# PassStat.net
KiCad netlist of a schematic drawn in Altium Designer
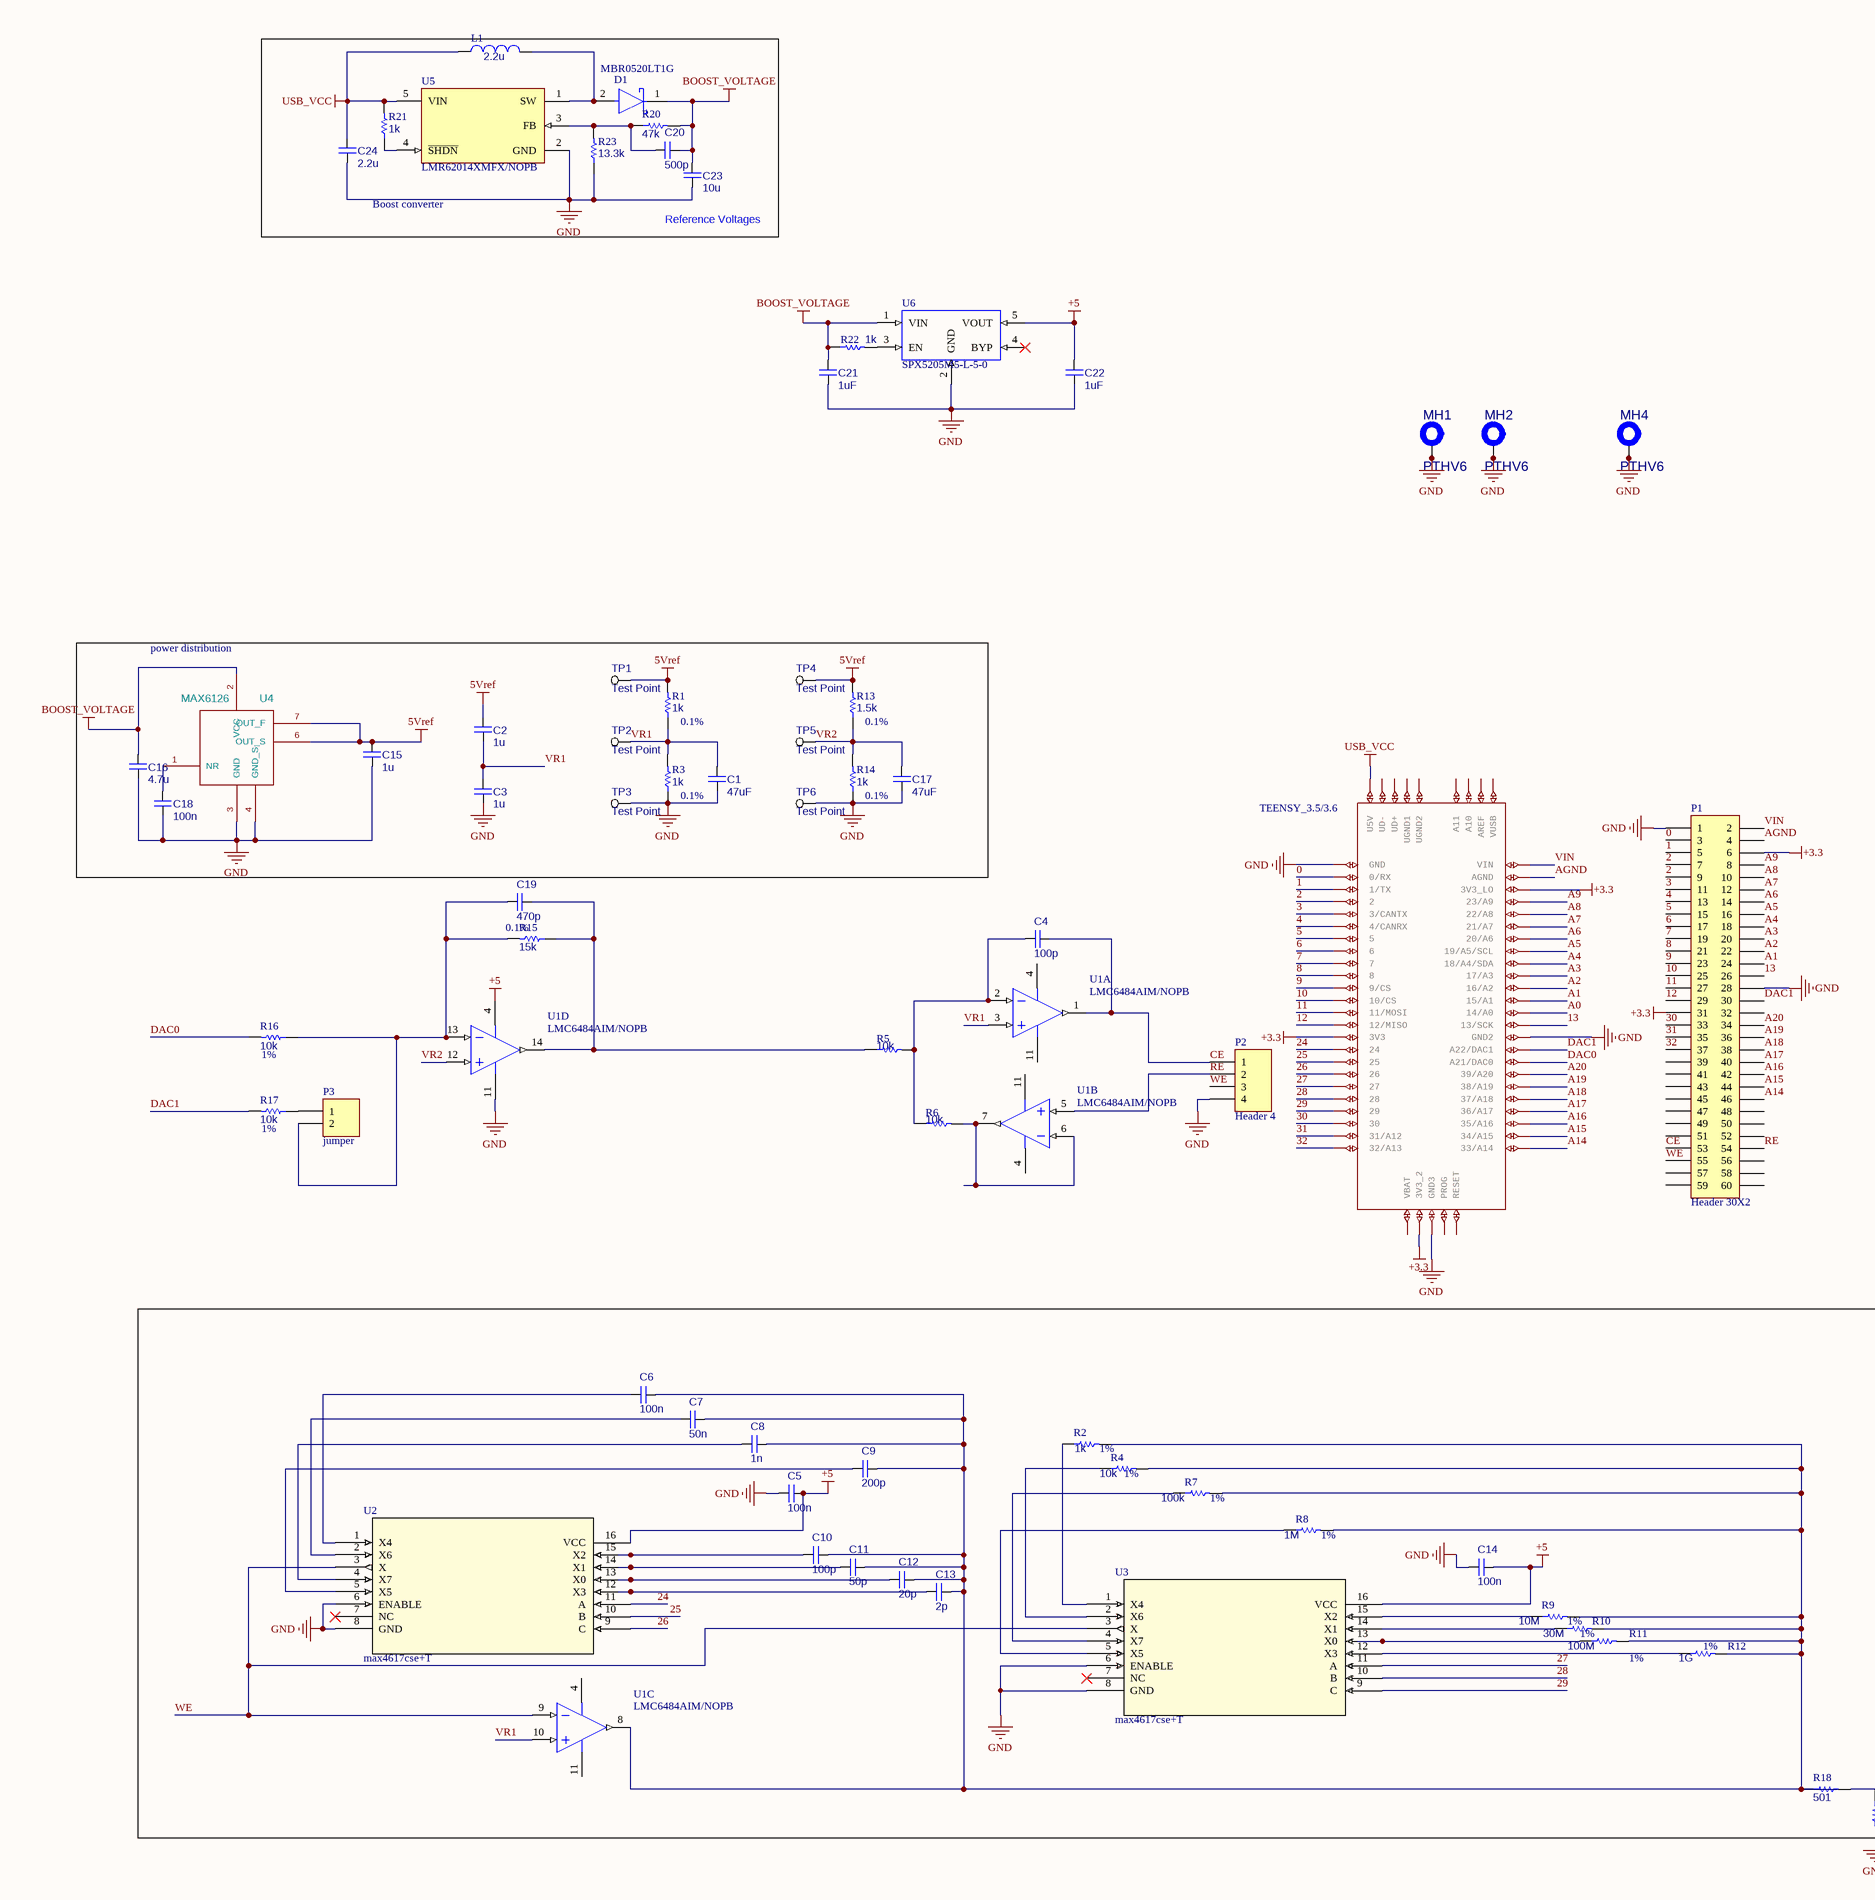
[diagram p0: PassStat.SchDoc, left]
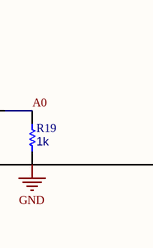
[diagram p1: PassStat.SchDoc, right]

(export (version "E")
  (design (tool "Eeschema 10.0.6"))
  (components
    (comp (ref "C1")
      (value "47uF")
      (footprint "C0805A")
      (description "Non-polarized capacitor")
      (fields (field (name "Comment") "Capacitor"))
      (libsource (lib "Space Concordia") (part "Capacitor"))
    )
    (comp (ref "C2")
      (value "1u")
      (footprint "C0805A")
      (description "Non-polarized capacitor")
      (fields (field (name "Comment") "Capacitor"))
      (libsource (lib "Space Concordia") (part "Capacitor"))
    )
    (comp (ref "C3")
      (value "1u")
      (footprint "C0805A")
      (description "Non-polarized capacitor")
      (fields (field (name "Comment") "Capacitor"))
      (libsource (lib "Space Concordia") (part "Capacitor"))
    )
    (comp (ref "C4")
      (value "100p")
      (footprint "C0805A")
      (description "Non-polarized capacitor")
      (fields (field (name "Comment") "Capacitor"))
      (libsource (lib "Space Concordia") (part "Capacitor"))
    )
    (comp (ref "C5")
      (value "100n")
      (footprint "C0805A")
      (description "Non-polarized capacitor")
      (fields (field (name "Comment") "Capacitor"))
      (libsource (lib "Space Concordia") (part "Capacitor"))
    )
    (comp (ref "C6")
      (value "100n")
      (footprint "C0805A")
      (description "Non-polarized capacitor")
      (fields (field (name "Comment") "Capacitor"))
      (libsource (lib "Space Concordia") (part "Capacitor"))
    )
    (comp (ref "C7")
      (value "50n")
      (footprint "C0805A")
      (description "Non-polarized capacitor")
      (fields (field (name "Comment") "Capacitor"))
      (libsource (lib "Space Concordia") (part "Capacitor"))
    )
    (comp (ref "C8")
      (value "1n")
      (footprint "C0805A")
      (description "Non-polarized capacitor")
      (fields (field (name "Comment") "Capacitor"))
      (libsource (lib "Space Concordia") (part "Capacitor"))
    )
    (comp (ref "C9")
      (value "200p")
      (footprint "C0805A")
      (description "Non-polarized capacitor")
      (fields (field (name "Comment") "Capacitor"))
      (libsource (lib "Space Concordia") (part "Capacitor"))
    )
    (comp (ref "C10")
      (value "100p")
      (footprint "C0805A")
      (description "Non-polarized capacitor")
      (fields (field (name "Comment") "Capacitor"))
      (libsource (lib "Space Concordia") (part "Capacitor"))
    )
    (comp (ref "C11")
      (value "50p")
      (footprint "C0805A")
      (description "Non-polarized capacitor")
      (fields (field (name "Comment") "Capacitor"))
      (libsource (lib "Space Concordia") (part "Capacitor"))
    )
    (comp (ref "C12")
      (value "20p")
      (footprint "C0805A")
      (description "Non-polarized capacitor")
      (fields (field (name "Comment") "Capacitor"))
      (libsource (lib "Space Concordia") (part "Capacitor"))
    )
    (comp (ref "C13")
      (value "2p")
      (footprint "C0805A")
      (description "Non-polarized capacitor")
      (fields (field (name "Comment") "Capacitor"))
      (libsource (lib "Space Concordia") (part "Capacitor"))
    )
    (comp (ref "C14")
      (value "100n")
      (footprint "C0805A")
      (description "Non-polarized capacitor")
      (fields (field (name "Comment") "Capacitor"))
      (libsource (lib "Space Concordia") (part "Capacitor"))
    )
    (comp (ref "C15")
      (value "1u")
      (footprint "C0805A")
      (description "Non-polarized capacitor")
      (fields (field (name "Comment") "Capacitor"))
      (libsource (lib "Space Concordia") (part "Capacitor"))
    )
    (comp (ref "C16")
      (value "4.7u")
      (footprint "C0805A")
      (description "Non-polarized capacitor")
      (fields (field (name "Comment") "Capacitor"))
      (libsource (lib "Space Concordia") (part "Capacitor"))
    )
    (comp (ref "C17")
      (value "47uF")
      (footprint "C0805A")
      (description "Non-polarized capacitor")
      (fields (field (name "Comment") "Capacitor"))
      (libsource (lib "Space Concordia") (part "Capacitor"))
    )
    (comp (ref "C18")
      (value "100n")
      (footprint "C0805A")
      (description "Non-polarized capacitor")
      (fields (field (name "Comment") "Capacitor"))
      (libsource (lib "Space Concordia") (part "Capacitor"))
    )
    (comp (ref "C19")
      (value "470p")
      (footprint "C0805A")
      (description "Non-polarized capacitor")
      (fields (field (name "Comment") "Capacitor"))
      (libsource (lib "Space Concordia") (part "Capacitor"))
    )
    (comp (ref "C20")
      (value "500p")
      (footprint "C0805A")
      (description "Non-polarized capacitor")
      (fields (field (name "Comment") "Capacitor"))
      (libsource (lib "Space Concordia") (part "Capacitor"))
    )
    (comp (ref "C21")
      (value "1uF")
      (footprint "C0603A")
      (description "Non-polarized capacitor")
      (fields (field (name "Comment") "Capacitor"))
      (libsource (lib "Space Concordia") (part "Capacitor"))
    )
    (comp (ref "C22")
      (value "1uF")
      (footprint "C0603A")
      (description "Non-polarized capacitor")
      (fields (field (name "Comment") "Capacitor"))
      (libsource (lib "Space Concordia") (part "Capacitor"))
    )
    (comp (ref "C23")
      (value "10u")
      (footprint "C0805A")
      (description "Non-polarized capacitor")
      (fields (field (name "Comment") "Capacitor"))
      (libsource (lib "Space Concordia") (part "Capacitor"))
    )
    (comp (ref "C24")
      (value "2.2u")
      (footprint "C0805A")
      (description "Non-polarized capacitor")
      (fields (field (name "Comment") "Capacitor"))
      (libsource (lib "Space Concordia") (part "Capacitor"))
    )
    (comp (ref "D1")
      (value "MBR0520LT1G")
      (footprint "FP-425-04-IPC_C")
      (description "DIODE SCHOTTKY 20V 500MA SOD123")
      (libsource (lib "Altium Content Vault") (part "1d6ec82d83fb6aee721767c19dac4b9"))
    )
    (comp (ref "L1")
      (value "2.2u")
      (footprint "L0805A")
      (description "Inductor, air coil")
      (fields (field (name "Comment") "2.2uH"))
      (libsource (lib "Space Concordia") (part "Inductor"))
    )
    (comp (ref "MCU")
      (value "TEENSY_3.5/3.6")
      (footprint "TEENSY_3.5/3.6")
      (libsource (lib "Space Concordia") (part "TEENSY_3.5/3.6"))
    )
    (comp (ref "MH1")
      (value "PTHV6")
      (footprint "PTHV6 4-40 Tight")
      (libsource (lib "Space Concordia") (part "PTHV6"))
    )
    (comp (ref "MH2")
      (value "PTHV6")
      (footprint "PTHV6 4-40 Tight")
      (libsource (lib "Space Concordia") (part "PTHV6"))
    )
    (comp (ref "MH4")
      (value "PTHV6")
      (footprint "PTHV6 4-40 Tight")
      (libsource (lib "Space Concordia") (part "PTHV6"))
    )
    (comp (ref "P1")
      (value "Header 30X2")
      (footprint "HDR2X30")
      (description "Header, 30-Pin, Dual row")
      (fields (field (name "PUBLISHER") "Altium Limited"))
      (libsource (lib "Space Concordia") (part "Header 30X2"))
    )
    (comp (ref "P2")
      (value "Header 4")
      (footprint "HDR1X4")
      (description "Header, 4-Pin")
      (fields (field (name "PUBLISHER") "Altium Limited"))
      (libsource (lib "Space Concordia") (part "Header 4H"))
    )
    (comp (ref "P3")
      (value "jumper")
      (footprint "HDR1X2")
      (description "Header, 2-Pin")
      (fields (field (name "PUBLISHER") "Altium Limited"))
      (libsource (lib "Space Concordia") (part "Header 2H"))
    )
    (comp (ref "R1")
      (value "1k")
      (footprint "R0805A")
      (description "Resistor")
      (fields (field (name "TOLERANCE") "0.1%"))
      (libsource (lib "Space Concordia") (part "Resistor"))
    )
    (comp (ref "R2")
      (value "1k")
      (footprint "R0805A")
      (description "Resistor")
      (fields (field (name "TOLERANCE") "1%"))
      (libsource (lib "Space Concordia") (part "Resistor"))
    )
    (comp (ref "R3")
      (value "1k")
      (footprint "R0805A")
      (description "Resistor")
      (fields (field (name "TOLERANCE") "0.1%"))
      (libsource (lib "Space Concordia") (part "Resistor"))
    )
    (comp (ref "R4")
      (value "10k")
      (footprint "R0805A")
      (description "Resistor")
      (fields (field (name "TOLERANCE") "1%"))
      (libsource (lib "Space Concordia") (part "Resistor"))
    )
    (comp (ref "R5")
      (value "10k")
      (footprint "R0805A")
      (description "Resistor")
      (libsource (lib "Space Concordia") (part "Resistor"))
    )
    (comp (ref "R6")
      (value "10k")
      (footprint "R0805A")
      (description "Resistor")
      (libsource (lib "Space Concordia") (part "Resistor"))
    )
    (comp (ref "R7")
      (value "100k")
      (footprint "R0805A")
      (description "Resistor")
      (fields (field (name "TOLERANCE") "1%"))
      (libsource (lib "Space Concordia") (part "Resistor"))
    )
    (comp (ref "R8")
      (value "1M")
      (footprint "R0805A")
      (description "Resistor")
      (fields (field (name "TOLERANCE") "1%"))
      (libsource (lib "Space Concordia") (part "Resistor"))
    )
    (comp (ref "R9")
      (value "10M")
      (footprint "R0805A")
      (description "Resistor")
      (fields (field (name "TOLERANCE") "1%"))
      (libsource (lib "Space Concordia") (part "Resistor"))
    )
    (comp (ref "R10")
      (value "30M")
      (footprint "R0805A")
      (description "Resistor")
      (fields (field (name "TOLERANCE") "1%"))
      (libsource (lib "Space Concordia") (part "Resistor"))
    )
    (comp (ref "R11")
      (value "100M")
      (footprint "R0805A")
      (description "Resistor")
      (fields (field (name "TOLERANCE") "1%"))
      (libsource (lib "Space Concordia") (part "Resistor"))
    )
    (comp (ref "R12")
      (value "1G")
      (footprint "R1206A")
      (description "Resistor")
      (fields (field (name "TOLERANCE") "1%"))
      (libsource (lib "Space Concordia") (part "Resistor"))
    )
    (comp (ref "R13")
      (value "1.5k")
      (footprint "R0805A")
      (description "Resistor")
      (fields (field (name "TOLERANCE") "0.1%"))
      (libsource (lib "Space Concordia") (part "Resistor"))
    )
    (comp (ref "R14")
      (value "1k")
      (footprint "R0805A")
      (description "Resistor")
      (fields (field (name "TOLERANCE") "0.1%"))
      (libsource (lib "Space Concordia") (part "Resistor"))
    )
    (comp (ref "R15")
      (value "15k")
      (footprint "R0805A")
      (description "Resistor")
      (fields (field (name "TOLERANCE") "0.1%"))
      (libsource (lib "Space Concordia") (part "Resistor"))
    )
    (comp (ref "R16")
      (value "10k")
      (footprint "R0805A")
      (description "Resistor")
      (fields (field (name "TOLERANCE") "1%"))
      (libsource (lib "Space Concordia") (part "Resistor"))
    )
    (comp (ref "R17")
      (value "10k")
      (footprint "R0805A")
      (description "Resistor")
      (fields (field (name "TOLERANCE") "1%"))
      (libsource (lib "Space Concordia") (part "Resistor"))
    )
    (comp (ref "R18")
      (value "501")
      (footprint "R0805A")
      (description "Resistor")
      (libsource (lib "Space Concordia") (part "Resistor"))
    )
    (comp (ref "R19")
      (value "1k")
      (footprint "R0805A")
      (description "Resistor")
      (libsource (lib "Space Concordia") (part "Resistor"))
    )
    (comp (ref "R20")
      (value "47k")
      (footprint "R0603A")
      (description "Resistor")
      (libsource (lib "Space Concordia") (part "Resistor"))
    )
    (comp (ref "R21")
      (value "1k")
      (footprint "R0603A")
      (description "Resistor")
      (libsource (lib "Space Concordia") (part "Resistor"))
    )
    (comp (ref "R22")
      (value "1k")
      (footprint "R0603A")
      (description "Resistor")
      (libsource (lib "Space Concordia") (part "Resistor"))
    )
    (comp (ref "R23")
      (value "13.3k")
      (footprint "R0603A")
      (description "Resistor")
      (libsource (lib "Space Concordia") (part "Resistor"))
    )
    (comp (ref "TP1")
      (value "Test Point")
      (footprint "TP-SMT-1mm")
      (description "In circuit test point for a net")
      (libsource (lib "Space Concordia") (part "Test Point"))
    )
    (comp (ref "TP2")
      (value "Test Point")
      (footprint "TP-SMT-1mm")
      (description "In circuit test point for a net")
      (libsource (lib "Space Concordia") (part "Test Point"))
    )
    (comp (ref "TP3")
      (value "Test Point")
      (footprint "TP-SMT-1mm")
      (description "In circuit test point for a net")
      (libsource (lib "Space Concordia") (part "Test Point"))
    )
    (comp (ref "TP4")
      (value "Test Point")
      (footprint "TP-SMT-1mm")
      (description "In circuit test point for a net")
      (libsource (lib "Space Concordia") (part "Test Point"))
    )
    (comp (ref "TP5")
      (value "Test Point")
      (footprint "TP-SMT-1mm")
      (description "In circuit test point for a net")
      (libsource (lib "Space Concordia") (part "Test Point"))
    )
    (comp (ref "TP6")
      (value "Test Point")
      (footprint "TP-SMT-1mm")
      (description "In circuit test point for a net")
      (libsource (lib "Space Concordia") (part "Test Point"))
    )
    (comp (ref "U1")
      (value "LMC6484AIM/NOPB")
      (footprint "D0014A_L")
      (description "CMOS Quad Rail to Rail Input and Output Operational Amplifier, 14-pin Narrow SOIC, Pb-Free")
      (fields (field (name "MANUFACTURER") "Texas Instruments"))
      (libsource (lib "Altium Content Vault") (part "AMP-OPA-LF147-14"))
    )
    (comp (ref "U2")
      (value "max4617cse+T")
      (footprint "21-0041_S16+1_MXM")
      (description "No Description Available")
      (libsource (lib "Space Concordia") (part "max4617cse+T"))
    )
    (comp (ref "U3")
      (value "max4617cse+T")
      (footprint "21-0041_S16+1_MXM")
      (description "No Description Available")
      (libsource (lib "Space Concordia") (part "max4617cse+T"))
    )
    (comp (ref "U4")
      (value "MAX6126")
      (footprint "SOIC-8_3.9x4.9mm_Pitch1.27mm")
      (description "Three Terminal Voltage Reference, 1 Output, 5V, BICMOS, PDSO8")
      (fields
        (field (name "MANUFACTURER") "Maxim")
        (field (name "MANUFACTURER PART NUMBER") "MAX6126AASA50+")
      )
      (libsource (lib "*") (part "MAX6126"))
    )
    (comp (ref "U5")
      (value "LMR62014XMFX/NOPB")
      (footprint "FP-DBV0005A-MFG")
      (description "IC REG BOOST ADJ 2A SOT23-5")
      (libsource (lib "Altium Content Vault") (part "7e5f9a72574904b8527a77c621fc30d"))
    )
    (comp (ref "U6")
      (value "SPX5205M5-L-5-0")
      (footprint "SOT95P280X145-5N")
      (description "Fixed Positive LDO Regulator, 5V, 0.35V Dropout, BIPolar, PDSO5")
      (libsource (lib "Space Concordia") (part "SPX5205M5-L-5-0-Symbol-1"))
    )
  )
  (nets
    (net (code "1") (name "+3.3") (class "Default")
      (node (ref "MCU") (pin "3V3") (pinfunction "3V3_3V3") (pintype "bidirectional"))
      (node (ref "MCU") (pin "3V3_2") (pinfunction "3V3_2_3V3_2") (pintype "bidirectional"))
      (node (ref "MCU") (pin "3V3_LO") (pinfunction "3V3_LO_3V3_LO") (pintype "bidirectional"))
      (node (ref "P1") (pin "31") (pinfunction "31_31") (pintype "passive"))
      (node (ref "P1") (pin "6") (pinfunction "6_6") (pintype "passive"))
    )
    (net (code "2") (name "+5") (class "Default")
      (node (ref "C14") (pin "2") (pinfunction "2_2") (pintype "passive"))
      (node (ref "C22") (pin "2") (pinfunction "2_2") (pintype "passive"))
      (node (ref "C5") (pin "2") (pinfunction "2_2") (pintype "passive"))
      (node (ref "U1") (pin "4") (pinfunction "V+_4") (pintype "power_in"))
      (node (ref "U2") (pin "16") (pinfunction "VCC_16") (pintype "power_in"))
      (node (ref "U3") (pin "16") (pinfunction "VCC_16") (pintype "power_in"))
      (node (ref "U6") (pin "5") (pinfunction "VOUT_5") (pintype "input"))
    )
    (net (code "3") (name "/0") (class "Default")
      (node (ref "MCU") (pin "0/RX") (pinfunction "0/RX_0/RX") (pintype "bidirectional"))
      (node (ref "P1") (pin "3") (pinfunction "3_3") (pintype "passive"))
    )
    (net (code "4") (name "/1") (class "Default")
      (node (ref "MCU") (pin "1/TX") (pinfunction "1/TX_1/TX") (pintype "bidirectional"))
      (node (ref "P1") (pin "5") (pinfunction "5_5") (pintype "passive"))
    )
    (net (code "5") (name "/2") (class "Default")
      (node (ref "MCU") (pin "2") (pinfunction "2_2") (pintype "bidirectional"))
      (node (ref "P1") (pin "7") (pinfunction "7_7") (pintype "passive"))
      (node (ref "P1") (pin "9") (pinfunction "9_9") (pintype "passive"))
    )
    (net (code "6") (name "/3") (class "Default")
      (node (ref "MCU") (pin "3/CANTX") (pinfunction "3/CANTX_3/CANTX") (pintype "bidirectional"))
      (node (ref "P1") (pin "11") (pinfunction "11_11") (pintype "passive"))
    )
    (net (code "7") (name "/4") (class "Default")
      (node (ref "MCU") (pin "4/CANRX") (pinfunction "4/CANRX_4/CANRX") (pintype "bidirectional"))
      (node (ref "P1") (pin "13") (pinfunction "13_13") (pintype "passive"))
    )
    (net (code "8") (name "/5") (class "Default")
      (node (ref "MCU") (pin "5") (pinfunction "5_5") (pintype "bidirectional"))
      (node (ref "P1") (pin "15") (pinfunction "15_15") (pintype "passive"))
    )
    (net (code "9") (name "/6") (class "Default")
      (node (ref "MCU") (pin "6") (pinfunction "6_6") (pintype "bidirectional"))
      (node (ref "P1") (pin "17") (pinfunction "17_17") (pintype "passive"))
    )
    (net (code "10") (name "/7") (class "Default")
      (node (ref "MCU") (pin "7") (pinfunction "7_7") (pintype "bidirectional"))
      (node (ref "P1") (pin "19") (pinfunction "19_19") (pintype "passive"))
    )
    (net (code "11") (name "/8") (class "Default")
      (node (ref "MCU") (pin "8") (pinfunction "8_8") (pintype "bidirectional"))
      (node (ref "P1") (pin "21") (pinfunction "21_21") (pintype "passive"))
    )
    (net (code "12") (name "/9") (class "Default")
      (node (ref "MCU") (pin "9/CS") (pinfunction "9/CS_9/CS") (pintype "bidirectional"))
      (node (ref "P1") (pin "23") (pinfunction "23_23") (pintype "passive"))
    )
    (net (code "13") (name "/10") (class "Default")
      (node (ref "MCU") (pin "10/CS") (pinfunction "10/CS_10/CS") (pintype "bidirectional"))
      (node (ref "P1") (pin "25") (pinfunction "25_25") (pintype "passive"))
    )
    (net (code "14") (name "/11") (class "Default")
      (node (ref "MCU") (pin "11/MOSI") (pinfunction "11/MOSI_11/MOSI") (pintype "bidirectional"))
      (node (ref "P1") (pin "27") (pinfunction "27_27") (pintype "passive"))
    )
    (net (code "15") (name "/12") (class "Default")
      (node (ref "MCU") (pin "12/MISO") (pinfunction "12/MISO_12/MISO") (pintype "bidirectional"))
      (node (ref "P1") (pin "29") (pinfunction "29_29") (pintype "passive"))
    )
    (net (code "16") (name "/13") (class "Default")
      (node (ref "MCU") (pin "13/SCK") (pinfunction "13/SCK_13/SCK") (pintype "bidirectional"))
      (node (ref "P1") (pin "26") (pinfunction "26_26") (pintype "passive"))
    )
    (net (code "17") (name "/24") (class "Default")
      (node (ref "MCU") (pin "24") (pinfunction "24_24") (pintype "bidirectional"))
      (node (ref "U2") (pin "11") (pinfunction "A_11") (pintype "input"))
    )
    (net (code "18") (name "/25") (class "Default")
      (node (ref "MCU") (pin "25") (pinfunction "25_25") (pintype "bidirectional"))
      (node (ref "U2") (pin "10") (pinfunction "B_10") (pintype "input"))
    )
    (net (code "19") (name "/26") (class "Default")
      (node (ref "MCU") (pin "26") (pinfunction "26_26") (pintype "bidirectional"))
      (node (ref "U2") (pin "9") (pinfunction "C_9") (pintype "input"))
    )
    (net (code "20") (name "/27") (class "Default")
      (node (ref "MCU") (pin "27") (pinfunction "27_27") (pintype "bidirectional"))
      (node (ref "U3") (pin "11") (pinfunction "A_11") (pintype "input"))
    )
    (net (code "21") (name "/28") (class "Default")
      (node (ref "MCU") (pin "28") (pinfunction "28_28") (pintype "bidirectional"))
      (node (ref "U3") (pin "10") (pinfunction "B_10") (pintype "input"))
    )
    (net (code "22") (name "/29") (class "Default")
      (node (ref "MCU") (pin "29") (pinfunction "29_29") (pintype "bidirectional"))
      (node (ref "U3") (pin "9") (pinfunction "C_9") (pintype "input"))
    )
    (net (code "23") (name "/30") (class "Default")
      (node (ref "MCU") (pin "30") (pinfunction "30_30") (pintype "bidirectional"))
      (node (ref "P1") (pin "33") (pinfunction "33_33") (pintype "passive"))
    )
    (net (code "24") (name "/31") (class "Default")
      (node (ref "MCU") (pin "31/A12") (pinfunction "31/A12_31/A12") (pintype "bidirectional"))
      (node (ref "P1") (pin "35") (pinfunction "35_35") (pintype "passive"))
    )
    (net (code "25") (name "/32") (class "Default")
      (node (ref "MCU") (pin "32/A13") (pinfunction "32/A13_32/A13") (pintype "bidirectional"))
      (node (ref "P1") (pin "37") (pinfunction "37_37") (pintype "passive"))
    )
    (net (code "26") (name "/<NO NET>") (class "Default")
      (node (ref "U1") (pin "4") (pinfunction "V+_4") (pintype "power_in"))
    )
    (net (code "27") (name "/A0") (class "Default")
      (node (ref "MCU") (pin "14/A0") (pinfunction "14/A0_14/A0") (pintype "bidirectional"))
      (node (ref "R18") (pin "2") (pinfunction "2_2") (pintype "passive"))
      (node (ref "R19") (pin "1") (pinfunction "1_1") (pintype "passive"))
    )
    (net (code "28") (name "/A1") (class "Default")
      (node (ref "MCU") (pin "15/A1") (pinfunction "15/A1_15/A1") (pintype "bidirectional"))
      (node (ref "P1") (pin "24") (pinfunction "24_24") (pintype "passive"))
    )
    (net (code "29") (name "/A2") (class "Default")
      (node (ref "MCU") (pin "16/A2") (pinfunction "16/A2_16/A2") (pintype "bidirectional"))
      (node (ref "P1") (pin "22") (pinfunction "22_22") (pintype "passive"))
    )
    (net (code "30") (name "/A3") (class "Default")
      (node (ref "MCU") (pin "17/A3") (pinfunction "17/A3_17/A3") (pintype "bidirectional"))
      (node (ref "P1") (pin "20") (pinfunction "20_20") (pintype "passive"))
    )
    (net (code "31") (name "/A4") (class "Default")
      (node (ref "MCU") (pin "18/A4/SDA") (pinfunction "18/A4/SDA_18/A4/SDA") (pintype "bidirectional"))
      (node (ref "P1") (pin "18") (pinfunction "18_18") (pintype "passive"))
    )
    (net (code "32") (name "/A5") (class "Default")
      (node (ref "MCU") (pin "19/A5/SCL") (pinfunction "19/A5/SCL_19/A5/SCL") (pintype "bidirectional"))
      (node (ref "P1") (pin "16") (pinfunction "16_16") (pintype "passive"))
    )
    (net (code "33") (name "/A6") (class "Default")
      (node (ref "MCU") (pin "20/A6") (pinfunction "20/A6_20/A6") (pintype "bidirectional"))
      (node (ref "P1") (pin "14") (pinfunction "14_14") (pintype "passive"))
    )
    (net (code "34") (name "/A7") (class "Default")
      (node (ref "MCU") (pin "21/A7") (pinfunction "21/A7_21/A7") (pintype "bidirectional"))
      (node (ref "P1") (pin "12") (pinfunction "12_12") (pintype "passive"))
    )
    (net (code "35") (name "/A8") (class "Default")
      (node (ref "MCU") (pin "22/A8") (pinfunction "22/A8_22/A8") (pintype "bidirectional"))
      (node (ref "P1") (pin "10") (pinfunction "10_10") (pintype "passive"))
    )
    (net (code "36") (name "/A9") (class "Default")
      (node (ref "MCU") (pin "23/A9") (pinfunction "23/A9_23/A9") (pintype "bidirectional"))
      (node (ref "P1") (pin "8") (pinfunction "8_8") (pintype "passive"))
    )
    (net (code "37") (name "/A14") (class "Default")
      (node (ref "MCU") (pin "33/A14") (pinfunction "33/A14_33/A14") (pintype "bidirectional"))
      (node (ref "P1") (pin "46") (pinfunction "46_46") (pintype "passive"))
    )
    (net (code "38") (name "/A15") (class "Default")
      (node (ref "MCU") (pin "34/A15") (pinfunction "34/A15_34/A15") (pintype "bidirectional"))
      (node (ref "P1") (pin "44") (pinfunction "44_44") (pintype "passive"))
    )
    (net (code "39") (name "/A16") (class "Default")
      (node (ref "MCU") (pin "35/A16") (pinfunction "35/A16_35/A16") (pintype "bidirectional"))
      (node (ref "P1") (pin "42") (pinfunction "42_42") (pintype "passive"))
    )
    (net (code "40") (name "/A17") (class "Default")
      (node (ref "MCU") (pin "36/A17") (pinfunction "36/A17_36/A17") (pintype "bidirectional"))
      (node (ref "P1") (pin "40") (pinfunction "40_40") (pintype "passive"))
    )
    (net (code "41") (name "/A18") (class "Default")
      (node (ref "MCU") (pin "37/A18") (pinfunction "37/A18_37/A18") (pintype "bidirectional"))
      (node (ref "P1") (pin "38") (pinfunction "38_38") (pintype "passive"))
    )
    (net (code "42") (name "/A19") (class "Default")
      (node (ref "MCU") (pin "38/A19") (pinfunction "38/A19_38/A19") (pintype "bidirectional"))
      (node (ref "P1") (pin "36") (pinfunction "36_36") (pintype "passive"))
    )
    (net (code "43") (name "/A20") (class "Default")
      (node (ref "MCU") (pin "39/A20") (pinfunction "39/A20_39/A20") (pintype "bidirectional"))
      (node (ref "P1") (pin "34") (pinfunction "34_34") (pintype "passive"))
    )
    (net (code "44") (name "/AGND") (class "Default")
      (node (ref "MCU") (pin "AGND") (pinfunction "AGND_AGND") (pintype "bidirectional"))
      (node (ref "P1") (pin "4") (pinfunction "4_4") (pintype "passive"))
    )
    (net (code "45") (name "/CE") (class "Default")
      (node (ref "C4") (pin "2") (pinfunction "2_2") (pintype "passive"))
      (node (ref "P1") (pin "53") (pinfunction "53_53") (pintype "passive"))
      (node (ref "P2") (pin "1") (pinfunction "1_1") (pintype "passive"))
      (node (ref "U1") (pin "1") (pinfunction "OUT1_1") (pintype "output"))
    )
    (net (code "46") (name "/DAC0") (class "Default")
      (node (ref "MCU") (pin "21/DAC0") (pinfunction "A21/DAC0_21/DAC0") (pintype "bidirectional"))
      (node (ref "R16") (pin "2") (pinfunction "2_2") (pintype "passive"))
    )
    (net (code "47") (name "/DAC1") (class "Default")
      (node (ref "MCU") (pin "A22/DAC1") (pinfunction "A22/DAC1_A22/DAC1") (pintype "bidirectional"))
      (node (ref "P1") (pin "30") (pinfunction "30_30") (pintype "passive"))
      (node (ref "R17") (pin "2") (pinfunction "2_2") (pintype "passive"))
    )
    (net (code "48") (name "/RE") (class "Default")
      (node (ref "P1") (pin "54") (pinfunction "54_54") (pintype "passive"))
      (node (ref "P2") (pin "2") (pinfunction "2_2") (pintype "passive"))
      (node (ref "U1") (pin "5") (pinfunction "IN2+_5") (pintype "input"))
    )
    (net (code "49") (name "/VIN") (class "Default")
      (node (ref "MCU") (pin "VIN") (pinfunction "VIN_VIN") (pintype "bidirectional"))
      (node (ref "P1") (pin "2") (pinfunction "2_2") (pintype "passive"))
    )
    (net (code "50") (name "/VR1") (class "Default")
      (node (ref "C1") (pin "2") (pinfunction "2_2") (pintype "passive"))
      (node (ref "C2") (pin "1") (pinfunction "1_1") (pintype "passive"))
      (node (ref "C3") (pin "2") (pinfunction "2_2") (pintype "passive"))
      (node (ref "R1") (pin "1") (pinfunction "1_1") (pintype "passive"))
      (node (ref "R3") (pin "2") (pinfunction "2_2") (pintype "passive"))
      (node (ref "TP2") (pin "1") (pinfunction "Pad_1") (pintype "passive"))
      (node (ref "U1") (pin "10") (pinfunction "IN3+_10") (pintype "input"))
      (node (ref "U1") (pin "3") (pinfunction "IN1+_3") (pintype "input"))
    )
    (net (code "51") (name "/VR2") (class "Default")
      (node (ref "C17") (pin "2") (pinfunction "2_2") (pintype "passive"))
      (node (ref "R13") (pin "1") (pinfunction "1_1") (pintype "passive"))
      (node (ref "R14") (pin "2") (pinfunction "2_2") (pintype "passive"))
      (node (ref "TP5") (pin "1") (pinfunction "Pad_1") (pintype "passive"))
      (node (ref "U1") (pin "12") (pinfunction "IN4+_12") (pintype "input"))
    )
    (net (code "52") (name "/WE") (class "Default")
      (node (ref "P1") (pin "55") (pinfunction "55_55") (pintype "passive"))
      (node (ref "P2") (pin "3") (pinfunction "3_3") (pintype "passive"))
      (node (ref "U1") (pin "9") (pinfunction "IN3-_9") (pintype "input"))
      (node (ref "U2") (pin "3") (pinfunction "X_3") (pintype "output"))
      (node (ref "U3") (pin "3") (pinfunction "X_3") (pintype "output"))
    )
    (net (code "53") (name "5Vref") (class "Default")
      (node (ref "C15") (pin "2") (pinfunction "2_2") (pintype "passive"))
      (node (ref "C2") (pin "2") (pinfunction "2_2") (pintype "passive"))
      (node (ref "R1") (pin "2") (pinfunction "2_2") (pintype "passive"))
      (node (ref "R13") (pin "2") (pinfunction "2_2") (pintype "passive"))
      (node (ref "TP1") (pin "1") (pinfunction "Pad_1") (pintype "passive"))
      (node (ref "TP4") (pin "1") (pinfunction "Pad_1") (pintype "passive"))
      (node (ref "U4") (pin "6") (pinfunction "OUT_S_6") (pintype "passive"))
      (node (ref "U4") (pin "7") (pinfunction "OUT_F_7") (pintype "passive"))
    )
    (net (code "54") (name "BOOST_VOLTAGE") (class "Default")
      (node (ref "C16") (pin "2") (pinfunction "2_2") (pintype "passive"))
      (node (ref "C20") (pin "1") (pinfunction "1_1") (pintype "passive"))
      (node (ref "C21") (pin "2") (pinfunction "2_2") (pintype "passive"))
      (node (ref "C23") (pin "2") (pinfunction "2_2") (pintype "passive"))
      (node (ref "D1") (pin "1") (pinfunction "C_1") (pintype "passive"))
      (node (ref "R20") (pin "2") (pinfunction "2_2") (pintype "passive"))
      (node (ref "R22") (pin "1") (pinfunction "1_1") (pintype "passive"))
      (node (ref "U4") (pin "2") (pinfunction "VCC_2") (pintype "passive"))
      (node (ref "U6") (pin "1") (pinfunction "VIN_1") (pintype "input"))
    )
    (net (code "55") (name "GND") (class "Default")
      (node (ref "C1") (pin "1") (pinfunction "1_1") (pintype "passive"))
      (node (ref "C14") (pin "1") (pinfunction "1_1") (pintype "passive"))
      (node (ref "C15") (pin "1") (pinfunction "1_1") (pintype "passive"))
      (node (ref "C16") (pin "1") (pinfunction "1_1") (pintype "passive"))
      (node (ref "C17") (pin "1") (pinfunction "1_1") (pintype "passive"))
      (node (ref "C18") (pin "1") (pinfunction "1_1") (pintype "passive"))
      (node (ref "C21") (pin "1") (pinfunction "1_1") (pintype "passive"))
      (node (ref "C22") (pin "1") (pinfunction "1_1") (pintype "passive"))
      (node (ref "C23") (pin "1") (pinfunction "1_1") (pintype "passive"))
      (node (ref "C24") (pin "1") (pinfunction "1_1") (pintype "passive"))
      (node (ref "C3") (pin "1") (pinfunction "1_1") (pintype "passive"))
      (node (ref "C5") (pin "1") (pinfunction "1_1") (pintype "passive"))
      (node (ref "MCU") (pin "GND") (pinfunction "GND_GND") (pintype "bidirectional"))
      (node (ref "MCU") (pin "GND2") (pinfunction "GND2_GND2") (pintype "bidirectional"))
      (node (ref "MCU") (pin "GND3") (pinfunction "GND3_GND3") (pintype "bidirectional"))
      (node (ref "MH1") (pin "1") (pinfunction "MH_1") (pintype "passive"))
      (node (ref "MH1") (pin "2") (pinfunction "V1_2") (pintype "passive"))
      (node (ref "MH1") (pin "3") (pinfunction "V2_3") (pintype "passive"))
      (node (ref "MH1") (pin "4") (pinfunction "V3_4") (pintype "passive"))
      (node (ref "MH1") (pin "5") (pinfunction "V4_5") (pintype "passive"))
      (node (ref "MH1") (pin "6") (pinfunction "V5_6") (pintype "passive"))
      (node (ref "MH1") (pin "7") (pinfunction "V6_7") (pintype "passive"))
      (node (ref "MH2") (pin "1") (pinfunction "MH_1") (pintype "passive"))
      (node (ref "MH2") (pin "2") (pinfunction "V1_2") (pintype "passive"))
      (node (ref "MH2") (pin "3") (pinfunction "V2_3") (pintype "passive"))
      (node (ref "MH2") (pin "4") (pinfunction "V3_4") (pintype "passive"))
      (node (ref "MH2") (pin "5") (pinfunction "V4_5") (pintype "passive"))
      (node (ref "MH2") (pin "6") (pinfunction "V5_6") (pintype "passive"))
      (node (ref "MH2") (pin "7") (pinfunction "V6_7") (pintype "passive"))
      (node (ref "MH4") (pin "1") (pinfunction "MH_1") (pintype "passive"))
      (node (ref "MH4") (pin "2") (pinfunction "V1_2") (pintype "passive"))
      (node (ref "MH4") (pin "3") (pinfunction "V2_3") (pintype "passive"))
      (node (ref "MH4") (pin "4") (pinfunction "V3_4") (pintype "passive"))
      (node (ref "MH4") (pin "5") (pinfunction "V4_5") (pintype "passive"))
      (node (ref "MH4") (pin "6") (pinfunction "V5_6") (pintype "passive"))
      (node (ref "MH4") (pin "7") (pinfunction "V6_7") (pintype "passive"))
      (node (ref "P1") (pin "1") (pinfunction "1_1") (pintype "passive"))
      (node (ref "P1") (pin "28") (pinfunction "28_28") (pintype "passive"))
      (node (ref "P2") (pin "4") (pinfunction "4_4") (pintype "passive"))
      (node (ref "R14") (pin "1") (pinfunction "1_1") (pintype "passive"))
      (node (ref "R19") (pin "2") (pinfunction "2_2") (pintype "passive"))
      (node (ref "R23") (pin "1") (pinfunction "1_1") (pintype "passive"))
      (node (ref "R3") (pin "1") (pinfunction "1_1") (pintype "passive"))
      (node (ref "TP3") (pin "1") (pinfunction "Pad_1") (pintype "passive"))
      (node (ref "TP6") (pin "1") (pinfunction "Pad_1") (pintype "passive"))
      (node (ref "U1") (pin "11") (pinfunction "V-_11") (pintype "power_in"))
      (node (ref "U2") (pin "6") (pinfunction "ENABLE_6") (pintype "input"))
      (node (ref "U2") (pin "8") (pinfunction "GND_8") (pintype "power_in"))
      (node (ref "U3") (pin "6") (pinfunction "ENABLE_6") (pintype "input"))
      (node (ref "U3") (pin "8") (pinfunction "GND_8") (pintype "power_in"))
      (node (ref "U4") (pin "3") (pinfunction "GND_3") (pintype "passive"))
      (node (ref "U4") (pin "4") (pinfunction "GND_S_4") (pintype "passive"))
      (node (ref "U5") (pin "2") (pinfunction "GND_2") (pintype "power_in"))
      (node (ref "U6") (pin "2") (pinfunction "GND_2") (pintype "input"))
    )
    (net (code "56") (name "Net-(D1-A)") (class "Default")
      (node (ref "D1") (pin "2") (pinfunction "A_2") (pintype "passive"))
      (node (ref "L1") (pin "2") (pinfunction "2_2") (pintype "passive"))
      (node (ref "U5") (pin "1") (pinfunction "SW_1") (pintype "power_in"))
    )
    (net (code "57") (name "Net-(P3-Pad1)") (class "Default")
      (node (ref "P3") (pin "1") (pinfunction "1_1") (pintype "passive"))
      (node (ref "R17") (pin "1") (pinfunction "1_1") (pintype "passive"))
    )
    (net (code "58") (name "Net-(U1A-IN1-)") (class "Default")
      (node (ref "C4") (pin "1") (pinfunction "1_1") (pintype "passive"))
      (node (ref "R5") (pin "2") (pinfunction "2_2") (pintype "passive"))
      (node (ref "R6") (pin "1") (pinfunction "1_1") (pintype "passive"))
      (node (ref "U1") (pin "2") (pinfunction "IN1-_2") (pintype "input"))
    )
    (net (code "59") (name "Net-(U1B-IN2-)") (class "Default")
      (node (ref "R6") (pin "2") (pinfunction "2_2") (pintype "passive"))
      (node (ref "U1") (pin "6") (pinfunction "IN2-_6") (pintype "input"))
      (node (ref "U1") (pin "7") (pinfunction "OUT2_7") (pintype "output"))
    )
    (net (code "60") (name "Net-(U1C-OUT3)") (class "Default")
      (node (ref "C10") (pin "2") (pinfunction "2_2") (pintype "passive"))
      (node (ref "C11") (pin "2") (pinfunction "2_2") (pintype "passive"))
      (node (ref "C12") (pin "2") (pinfunction "2_2") (pintype "passive"))
      (node (ref "C13") (pin "2") (pinfunction "2_2") (pintype "passive"))
      (node (ref "C6") (pin "2") (pinfunction "2_2") (pintype "passive"))
      (node (ref "C7") (pin "2") (pinfunction "2_2") (pintype "passive"))
      (node (ref "C8") (pin "2") (pinfunction "2_2") (pintype "passive"))
      (node (ref "C9") (pin "2") (pinfunction "2_2") (pintype "passive"))
      (node (ref "R10") (pin "2") (pinfunction "2_2") (pintype "passive"))
      (node (ref "R11") (pin "2") (pinfunction "2_2") (pintype "passive"))
      (node (ref "R12") (pin "2") (pinfunction "2_2") (pintype "passive"))
      (node (ref "R18") (pin "1") (pinfunction "1_1") (pintype "passive"))
      (node (ref "R2") (pin "2") (pinfunction "2_2") (pintype "passive"))
      (node (ref "R4") (pin "2") (pinfunction "2_2") (pintype "passive"))
      (node (ref "R7") (pin "2") (pinfunction "2_2") (pintype "passive"))
      (node (ref "R8") (pin "2") (pinfunction "2_2") (pintype "passive"))
      (node (ref "R9") (pin "2") (pinfunction "2_2") (pintype "passive"))
      (node (ref "U1") (pin "8") (pinfunction "OUT3_8") (pintype "output"))
    )
    (net (code "61") (name "Net-(U1D-IN4-)") (class "Default")
      (node (ref "C19") (pin "2") (pinfunction "2_2") (pintype "passive"))
      (node (ref "P3") (pin "2") (pinfunction "2_2") (pintype "passive"))
      (node (ref "R15") (pin "2") (pinfunction "2_2") (pintype "passive"))
      (node (ref "R16") (pin "1") (pinfunction "1_1") (pintype "passive"))
      (node (ref "U1") (pin "13") (pinfunction "IN4-_13") (pintype "input"))
    )
    (net (code "62") (name "Net-(U1D-OUT4)") (class "Default")
      (node (ref "C19") (pin "1") (pinfunction "1_1") (pintype "passive"))
      (node (ref "R15") (pin "1") (pinfunction "1_1") (pintype "passive"))
      (node (ref "R5") (pin "1") (pinfunction "1_1") (pintype "passive"))
      (node (ref "U1") (pin "14") (pinfunction "OUT4_14") (pintype "output"))
    )
    (net (code "63") (name "Net-(U2-X0)") (class "Default")
      (node (ref "C12") (pin "1") (pinfunction "1_1") (pintype "passive"))
      (node (ref "U2") (pin "13") (pinfunction "X0_13") (pintype "input"))
    )
    (net (code "64") (name "Net-(U2-X1)") (class "Default")
      (node (ref "C11") (pin "1") (pinfunction "1_1") (pintype "passive"))
      (node (ref "U2") (pin "14") (pinfunction "X1_14") (pintype "input"))
    )
    (net (code "65") (name "Net-(U2-X2)") (class "Default")
      (node (ref "C10") (pin "1") (pinfunction "1_1") (pintype "passive"))
      (node (ref "U2") (pin "15") (pinfunction "X2_15") (pintype "input"))
    )
    (net (code "66") (name "Net-(U2-X3)") (class "Default")
      (node (ref "C13") (pin "1") (pinfunction "1_1") (pintype "passive"))
      (node (ref "U2") (pin "12") (pinfunction "X3_12") (pintype "input"))
    )
    (net (code "67") (name "Net-(U2-X4)") (class "Default")
      (node (ref "C6") (pin "1") (pinfunction "1_1") (pintype "passive"))
      (node (ref "U2") (pin "1") (pinfunction "X4_1") (pintype "input"))
    )
    (net (code "68") (name "Net-(U2-X5)") (class "Default")
      (node (ref "C9") (pin "1") (pinfunction "1_1") (pintype "passive"))
      (node (ref "U2") (pin "5") (pinfunction "X5_5") (pintype "input"))
    )
    (net (code "69") (name "Net-(U2-X6)") (class "Default")
      (node (ref "C7") (pin "1") (pinfunction "1_1") (pintype "passive"))
      (node (ref "U2") (pin "2") (pinfunction "X6_2") (pintype "input"))
    )
    (net (code "70") (name "Net-(U2-X7)") (class "Default")
      (node (ref "C8") (pin "1") (pinfunction "1_1") (pintype "passive"))
      (node (ref "U2") (pin "4") (pinfunction "X7_4") (pintype "input"))
    )
    (net (code "71") (name "Net-(U3-X0)") (class "Default")
      (node (ref "R11") (pin "1") (pinfunction "1_1") (pintype "passive"))
      (node (ref "U3") (pin "13") (pinfunction "X0_13") (pintype "input"))
    )
    (net (code "72") (name "Net-(U3-X1)") (class "Default")
      (node (ref "R10") (pin "1") (pinfunction "1_1") (pintype "passive"))
      (node (ref "U3") (pin "14") (pinfunction "X1_14") (pintype "input"))
    )
    (net (code "73") (name "Net-(U3-X2)") (class "Default")
      (node (ref "R9") (pin "1") (pinfunction "1_1") (pintype "passive"))
      (node (ref "U3") (pin "15") (pinfunction "X2_15") (pintype "input"))
    )
    (net (code "74") (name "Net-(U3-X3)") (class "Default")
      (node (ref "R12") (pin "1") (pinfunction "1_1") (pintype "passive"))
      (node (ref "U3") (pin "12") (pinfunction "X3_12") (pintype "input"))
    )
    (net (code "75") (name "Net-(U3-X4)") (class "Default")
      (node (ref "R2") (pin "1") (pinfunction "1_1") (pintype "passive"))
      (node (ref "U3") (pin "1") (pinfunction "X4_1") (pintype "input"))
    )
    (net (code "76") (name "Net-(U3-X5)") (class "Default")
      (node (ref "R8") (pin "1") (pinfunction "1_1") (pintype "passive"))
      (node (ref "U3") (pin "5") (pinfunction "X5_5") (pintype "input"))
    )
    (net (code "77") (name "Net-(U3-X6)") (class "Default")
      (node (ref "R4") (pin "1") (pinfunction "1_1") (pintype "passive"))
      (node (ref "U3") (pin "2") (pinfunction "X6_2") (pintype "input"))
    )
    (net (code "78") (name "Net-(U3-X7)") (class "Default")
      (node (ref "R7") (pin "1") (pinfunction "1_1") (pintype "passive"))
      (node (ref "U3") (pin "4") (pinfunction "X7_4") (pintype "input"))
    )
    (net (code "79") (name "Net-(U4-NR)") (class "Default")
      (node (ref "C18") (pin "2") (pinfunction "2_2") (pintype "passive"))
      (node (ref "U4") (pin "1") (pinfunction "NR_1") (pintype "passive"))
    )
    (net (code "80") (name "Net-(U5-FB)") (class "Default")
      (node (ref "C20") (pin "2") (pinfunction "2_2") (pintype "passive"))
      (node (ref "R20") (pin "1") (pinfunction "1_1") (pintype "passive"))
      (node (ref "R23") (pin "2") (pinfunction "2_2") (pintype "passive"))
      (node (ref "U5") (pin "3") (pinfunction "FB_3") (pintype "input"))
    )
    (net (code "81") (name "Net-(U5-~{SHDN})") (class "Default")
      (node (ref "R21") (pin "1") (pinfunction "1_1") (pintype "passive"))
      (node (ref "U5") (pin "4") (pinfunction "~{SHDN}_4") (pintype "input"))
    )
    (net (code "82") (name "Net-(U6-EN)") (class "Default")
      (node (ref "R22") (pin "2") (pinfunction "2_2") (pintype "passive"))
      (node (ref "U6") (pin "3") (pinfunction "EN_3") (pintype "input"))
    )
    (net (code "83") (name "USB_VCC") (class "Default")
      (node (ref "C24") (pin "2") (pinfunction "2_2") (pintype "passive"))
      (node (ref "L1") (pin "1") (pinfunction "1_1") (pintype "passive"))
      (node (ref "MCU") (pin "U5V") (pinfunction "U5V_U5V") (pintype "bidirectional"))
      (node (ref "R21") (pin "2") (pinfunction "2_2") (pintype "passive"))
      (node (ref "U5") (pin "5") (pinfunction "VIN_5") (pintype "power_in"))
    )
    (net (code "84") (name "unconnected-(MCU-PadA10)") (class "Default")
      (node (ref "MCU") (pin "A10") (pinfunction "A10_A10") (pintype "bidirectional"))
    )
    (net (code "85") (name "unconnected-(MCU-PadA11)") (class "Default")
      (node (ref "MCU") (pin "A11") (pinfunction "A11_A11") (pintype "bidirectional"))
    )
    (net (code "86") (name "unconnected-(MCU-PadAREF)") (class "Default")
      (node (ref "MCU") (pin "AREF") (pinfunction "AREF_AREF") (pintype "bidirectional"))
    )
    (net (code "87") (name "unconnected-(MCU-PadPROG)") (class "Default")
      (node (ref "MCU") (pin "PROG") (pinfunction "PROG_PROG") (pintype "bidirectional"))
    )
    (net (code "88") (name "unconnected-(MCU-PadRESET)") (class "Default")
      (node (ref "MCU") (pin "RESET") (pinfunction "RESET_RESET") (pintype "bidirectional"))
    )
    (net (code "89") (name "unconnected-(MCU-PadUD+)") (class "Default")
      (node (ref "MCU") (pin "UD+") (pinfunction "UD+_UD+") (pintype "bidirectional"))
    )
    (net (code "90") (name "unconnected-(MCU-PadUD-)") (class "Default")
      (node (ref "MCU") (pin "UD-") (pinfunction "UD-_UD-") (pintype "bidirectional"))
    )
    (net (code "91") (name "unconnected-(MCU-PadUGND1)") (class "Default")
      (node (ref "MCU") (pin "UGND1") (pinfunction "UGND1_UGND1") (pintype "bidirectional"))
    )
    (net (code "92") (name "unconnected-(MCU-PadUGND2)") (class "Default")
      (node (ref "MCU") (pin "UGND2") (pinfunction "UGND2_UGND2") (pintype "bidirectional"))
    )
    (net (code "93") (name "unconnected-(MCU-PadVBAT)") (class "Default")
      (node (ref "MCU") (pin "VBAT") (pinfunction "VBAT_VBAT") (pintype "bidirectional"))
    )
    (net (code "94") (name "unconnected-(MCU-PadVUSB)") (class "Default")
      (node (ref "MCU") (pin "VUSB") (pinfunction "VUSB_VUSB") (pintype "bidirectional"))
    )
    (net (code "95") (name "unconnected-(P1-Pad32)") (class "Default")
      (node (ref "P1") (pin "32") (pinfunction "32_32") (pintype "passive"))
    )
    (net (code "96") (name "unconnected-(P1-Pad39)") (class "Default")
      (node (ref "P1") (pin "39") (pinfunction "39_39") (pintype "passive"))
    )
    (net (code "97") (name "unconnected-(P1-Pad41)") (class "Default")
      (node (ref "P1") (pin "41") (pinfunction "41_41") (pintype "passive"))
    )
    (net (code "98") (name "unconnected-(P1-Pad43)") (class "Default")
      (node (ref "P1") (pin "43") (pinfunction "43_43") (pintype "passive"))
    )
    (net (code "99") (name "unconnected-(P1-Pad45)") (class "Default")
      (node (ref "P1") (pin "45") (pinfunction "45_45") (pintype "passive"))
    )
    (net (code "100") (name "unconnected-(P1-Pad47)") (class "Default")
      (node (ref "P1") (pin "47") (pinfunction "47_47") (pintype "passive"))
    )
    (net (code "101") (name "unconnected-(P1-Pad48)") (class "Default")
      (node (ref "P1") (pin "48") (pinfunction "48_48") (pintype "passive"))
    )
    (net (code "102") (name "unconnected-(P1-Pad49)") (class "Default")
      (node (ref "P1") (pin "49") (pinfunction "49_49") (pintype "passive"))
    )
    (net (code "103") (name "unconnected-(P1-Pad50)") (class "Default")
      (node (ref "P1") (pin "50") (pinfunction "50_50") (pintype "passive"))
    )
    (net (code "104") (name "unconnected-(P1-Pad51)") (class "Default")
      (node (ref "P1") (pin "51") (pinfunction "51_51") (pintype "passive"))
    )
    (net (code "105") (name "unconnected-(P1-Pad52)") (class "Default")
      (node (ref "P1") (pin "52") (pinfunction "52_52") (pintype "passive"))
    )
    (net (code "106") (name "unconnected-(P1-Pad56)") (class "Default")
      (node (ref "P1") (pin "56") (pinfunction "56_56") (pintype "passive"))
    )
    (net (code "107") (name "unconnected-(P1-Pad57)") (class "Default")
      (node (ref "P1") (pin "57") (pinfunction "57_57") (pintype "passive"))
    )
    (net (code "108") (name "unconnected-(P1-Pad58)") (class "Default")
      (node (ref "P1") (pin "58") (pinfunction "58_58") (pintype "passive"))
    )
    (net (code "109") (name "unconnected-(P1-Pad59)") (class "Default")
      (node (ref "P1") (pin "59") (pinfunction "59_59") (pintype "passive"))
    )
    (net (code "110") (name "unconnected-(P1-Pad60)") (class "Default")
      (node (ref "P1") (pin "60") (pinfunction "60_60") (pintype "passive"))
    )
    (net (code "111") (name "unconnected-(U1A-V--Pad11)") (class "Default")
      (node (ref "U1") (pin "11") (pinfunction "V-_11") (pintype "power_in"))
    )
    (net (code "112") (name "unconnected-(U1B-V+-Pad4)") (class "Default")
      (node (ref "U1") (pin "4") (pinfunction "V+_4") (pintype "power_in"))
    )
    (net (code "113") (name "unconnected-(U1B-V--Pad11)") (class "Default")
      (node (ref "U1") (pin "11") (pinfunction "V-_11") (pintype "power_in"))
    )
    (net (code "114") (name "unconnected-(U1C-V+-Pad4)") (class "Default")
      (node (ref "U1") (pin "4") (pinfunction "V+_4") (pintype "power_in"))
    )
    (net (code "115") (name "unconnected-(U1C-V--Pad11)") (class "Default")
      (node (ref "U1") (pin "11") (pinfunction "V-_11") (pintype "power_in"))
    )
    (net (code "116") (name "unconnected-(U2-NC-Pad7)") (class "Default")
      (node (ref "U2") (pin "7") (pinfunction "NC_7") (pintype "passive+no_connect"))
    )
    (net (code "117") (name "unconnected-(U3-NC-Pad7)") (class "Default")
      (node (ref "U3") (pin "7") (pinfunction "NC_7") (pintype "passive+no_connect"))
    )
    (net (code "118") (name "unconnected-(U6-BYP-Pad4)") (class "Default")
      (node (ref "U6") (pin "4") (pinfunction "BYP_4") (pintype "input+no_connect"))
    )
  )
)
